# H3BR2.net
KiCad netlist of a schematic drawn in EAGLE
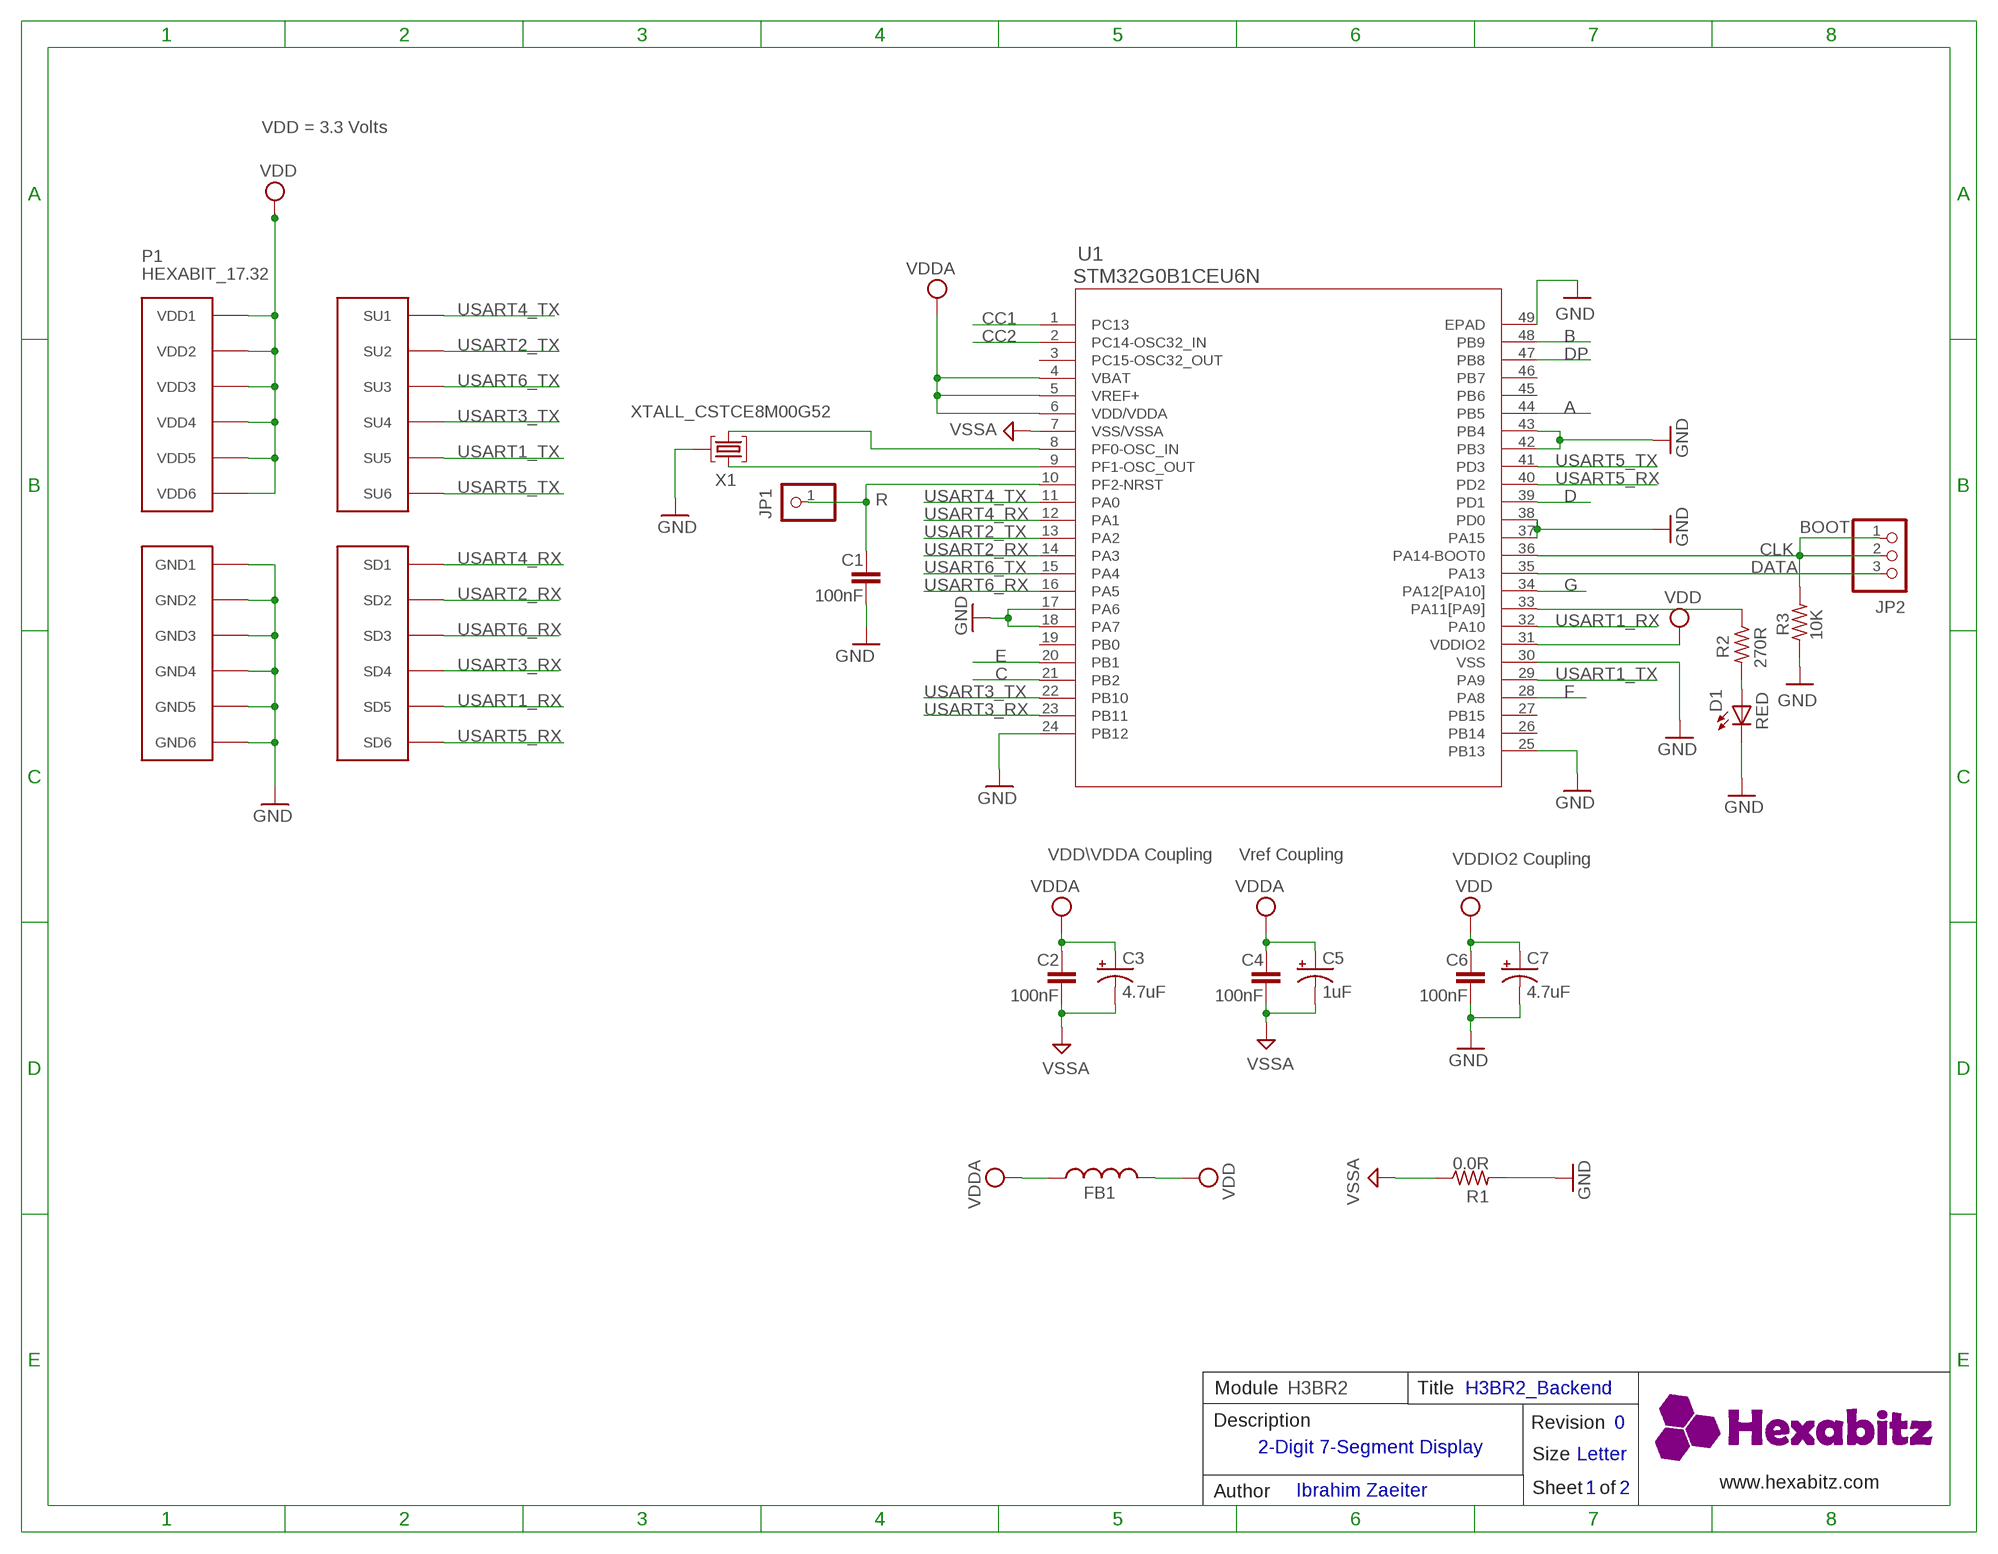
[diagram p0: schematic, sheet 1]
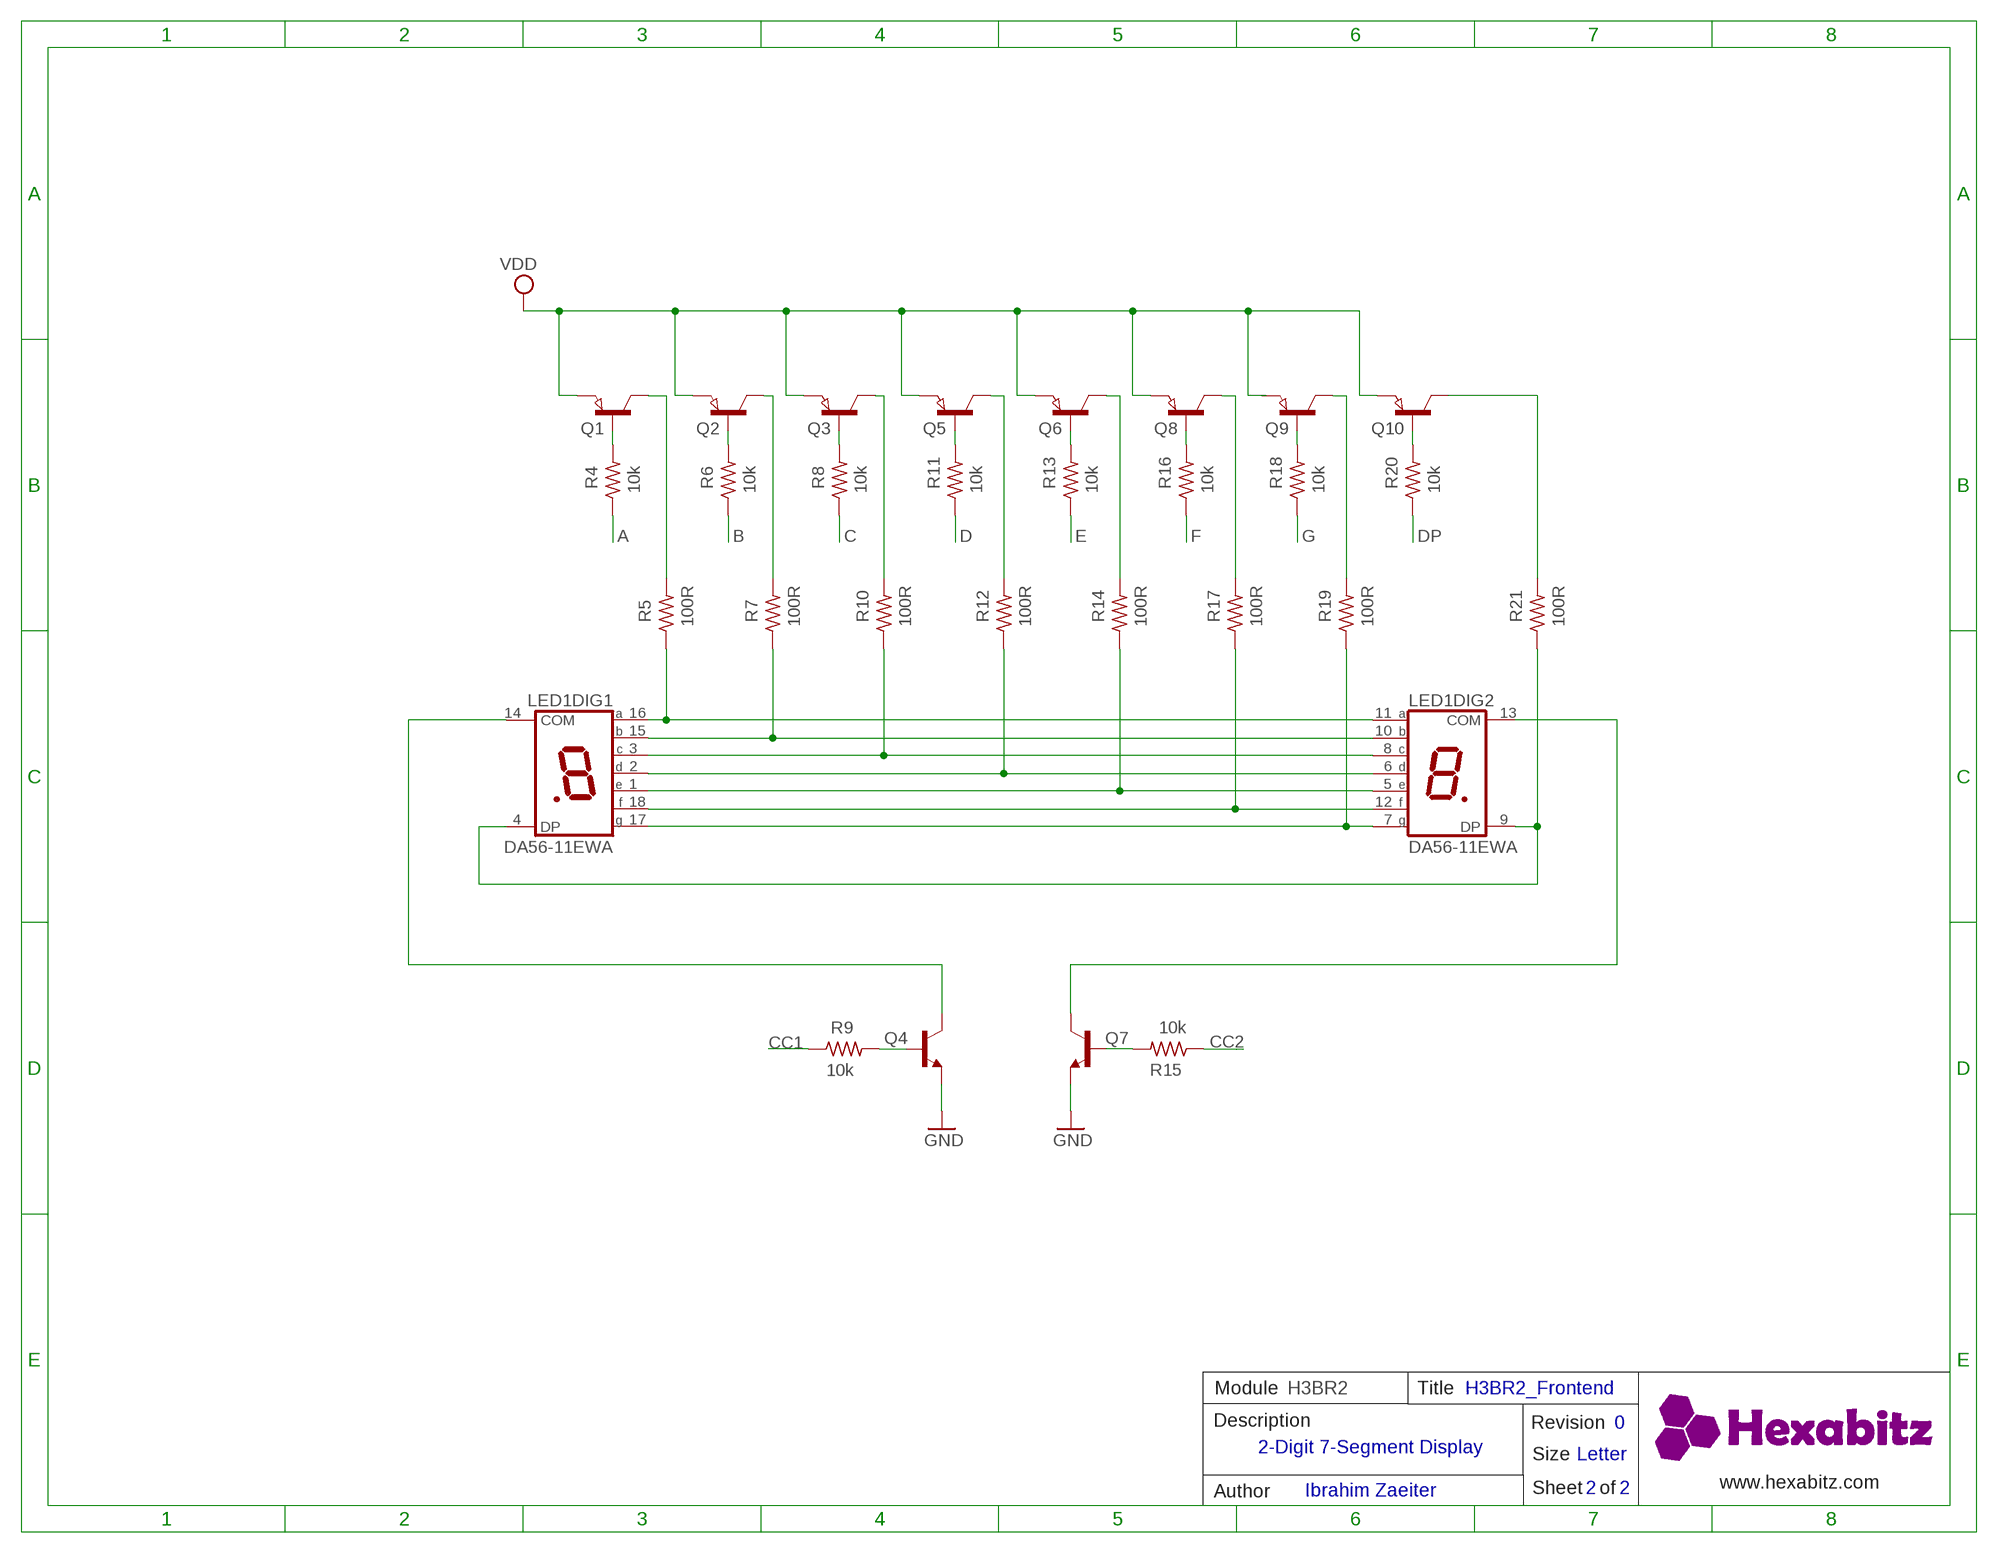
[diagram p1: schematic, sheet 2]

(export (version "E")
  (design (tool "Eeschema 10.0.6"))
  (components
    (comp (ref "C1")
      (value "100nF")
      (footprint "eagle-import:C-0402")
      (libsource (lib "eagle-import") (part "C-0402"))
    )
    (comp (ref "C2")
      (value "100nF")
      (footprint "eagle-import:C-0402")
      (libsource (lib "eagle-import") (part "C-0402"))
    )
    (comp (ref "C3")
      (value "4.7uF")
      (footprint "eagle-import:C-0805-POL")
      (libsource (lib "eagle-import") (part "C-0805-POL"))
    )
    (comp (ref "C4")
      (value "100nF")
      (footprint "eagle-import:C-0402")
      (libsource (lib "eagle-import") (part "C-0402"))
    )
    (comp (ref "C5")
      (value "1uF")
      (footprint "eagle-import:C-0805-POL")
      (libsource (lib "eagle-import") (part "C-0805-POL"))
    )
    (comp (ref "C6")
      (value "100nF")
      (footprint "eagle-import:C-0402")
      (libsource (lib "eagle-import") (part "C-0402"))
    )
    (comp (ref "C7")
      (value "4.7uF")
      (footprint "eagle-import:C-0805-POL")
      (libsource (lib "eagle-import") (part "C-0805-POL"))
    )
    (comp (ref "D1")
      (value "RED")
      (footprint "eagle-import:VLMS1300-GS08")
      (fields
        (field (name "MPN") "VLMS1300-GS08")
        (field (name "MFN") "Vishay")
        (field (name "MPN_1") "VLMS1300-GS08")
        (field (name "OCTOPART_URL") "https://octopart.com/vlms1300-gs08-vishay-21709201?r=sp&s=_gcP4_q8T1SC6PJQPTQ9yA")
      )
      (libsource (lib "eagle-import") (part "VLMS1300-GS08"))
    )
    (comp (ref "FB1")
      (value "FB-0603")
      (footprint "eagle-import:FB-0603")
      (libsource (lib "eagle-import") (part "FB-0603"))
    )
    (comp (ref "JP1")
      (value "R")
      (footprint "eagle-import:1X01")
      (fields (field (name "MPN") "87227-1"))
      (libsource (lib "eagle-import") (part "PINHD-1X1"))
    )
    (comp (ref "JP2")
      (value "PINHD-1X3")
      (footprint "eagle-import:1X03")
      (libsource (lib "eagle-import") (part "PINHD-1X3"))
    )
    (comp (ref "P1")
      (value "HEXABIT_17.32")
      (footprint "eagle-import:HEXABIT_17.32")
      (libsource (lib "eagle-import") (part "HEXABIT_?17.32"))
    )
    (comp (ref "R1")
      (value "0.0R")
      (footprint "eagle-import:R-0402")
      (libsource (lib "eagle-import") (part "R-0402"))
    )
    (comp (ref "R2")
      (value "270R")
      (footprint "eagle-import:R-0603")
      (libsource (lib "eagle-import") (part "R-0603"))
    )
    (comp (ref "R3")
      (value "10K")
      (footprint "eagle-import:R-0402")
      (libsource (lib "eagle-import") (part "R-0402"))
    )
    (comp (ref "U1")
      (value "STM32G0B1CEU6N")
      (footprint "eagle-import:QFN_B1CEU6_STM-L")
      (libsource (lib "eagle-import") (part "STM32G0B1CEU6N"))
    )
    (comp (ref "X1")
      (value "XTALL_CSTCE8M00G52")
      (footprint "eagle-import:XTALL_CSTCE8M00G52")
      (fields (field (name "MPN") "CSTCE8M00G52Z-R0"))
      (libsource (lib "eagle-import") (part "XTALL_CSTCE8M00G52"))
    )
    (comp (ref "LED1")
      (value "DA56-11EWA")
      (footprint "eagle-import:DA56")
      (fields (field (name "MF") "Lite-On") (field (name "MPN") "LTD-6940HR"))
      (libsource (lib "eagle-import") (part "DA56-11EWA"))
    )
    (comp (ref "Q1")
      (value "SEMICON-SMD-IPC_PNP-TRANSISTOR_SOT23")
      (footprint "eagle-import:SEMICON-SMD-IPC_SOT23")
      (libsource (lib "eagle-import") (part "SEMICON-SMD-IPC_PNP-TRANSISTOR_SOT23"))
    )
    (comp (ref "Q2")
      (value "SEMICON-SMD-IPC_PNP-TRANSISTOR_SOT23")
      (footprint "eagle-import:SEMICON-SMD-IPC_SOT23")
      (libsource (lib "eagle-import") (part "SEMICON-SMD-IPC_PNP-TRANSISTOR_SOT23"))
    )
    (comp (ref "Q3")
      (value "SEMICON-SMD-IPC_PNP-TRANSISTOR_SOT23")
      (footprint "eagle-import:SEMICON-SMD-IPC_SOT23")
      (libsource (lib "eagle-import") (part "SEMICON-SMD-IPC_PNP-TRANSISTOR_SOT23"))
    )
    (comp (ref "Q4")
      (value "MMBT3904LT1")
      (footprint "eagle-import:MMBT3904LT1")
      (libsource (lib "eagle-import") (part "MMBT3904LT1"))
    )
    (comp (ref "Q5")
      (value "SEMICON-SMD-IPC_PNP-TRANSISTOR_SOT23")
      (footprint "eagle-import:SEMICON-SMD-IPC_SOT23")
      (libsource (lib "eagle-import") (part "SEMICON-SMD-IPC_PNP-TRANSISTOR_SOT23"))
    )
    (comp (ref "Q6")
      (value "SEMICON-SMD-IPC_PNP-TRANSISTOR_SOT23")
      (footprint "eagle-import:SEMICON-SMD-IPC_SOT23")
      (libsource (lib "eagle-import") (part "SEMICON-SMD-IPC_PNP-TRANSISTOR_SOT23"))
    )
    (comp (ref "Q7")
      (value "MMBT3904LT1")
      (footprint "eagle-import:MMBT3904LT1")
      (libsource (lib "eagle-import") (part "MMBT3904LT1"))
    )
    (comp (ref "Q8")
      (value "SEMICON-SMD-IPC_PNP-TRANSISTOR_SOT23")
      (footprint "eagle-import:SEMICON-SMD-IPC_SOT23")
      (libsource (lib "eagle-import") (part "SEMICON-SMD-IPC_PNP-TRANSISTOR_SOT23"))
    )
    (comp (ref "Q9")
      (value "SEMICON-SMD-IPC_PNP-TRANSISTOR_SOT23")
      (footprint "eagle-import:SEMICON-SMD-IPC_SOT23")
      (libsource (lib "eagle-import") (part "SEMICON-SMD-IPC_PNP-TRANSISTOR_SOT23"))
    )
    (comp (ref "Q10")
      (value "SEMICON-SMD-IPC_PNP-TRANSISTOR_SOT23")
      (footprint "eagle-import:SEMICON-SMD-IPC_SOT23")
      (libsource (lib "eagle-import") (part "SEMICON-SMD-IPC_PNP-TRANSISTOR_SOT23"))
    )
    (comp (ref "R4")
      (value "10k")
      (footprint "eagle-import:R-0402")
      (libsource (lib "eagle-import") (part "R-0402"))
    )
    (comp (ref "R5")
      (value "100R")
      (footprint "eagle-import:R-0402")
      (libsource (lib "eagle-import") (part "R-0402"))
    )
    (comp (ref "R6")
      (value "10k")
      (footprint "eagle-import:R-0402")
      (libsource (lib "eagle-import") (part "R-0402"))
    )
    (comp (ref "R7")
      (value "100R")
      (footprint "eagle-import:R-0402")
      (libsource (lib "eagle-import") (part "R-0402"))
    )
    (comp (ref "R8")
      (value "10k")
      (footprint "eagle-import:R-0402")
      (libsource (lib "eagle-import") (part "R-0402"))
    )
    (comp (ref "R9")
      (value "10k")
      (footprint "eagle-import:R-0402")
      (libsource (lib "eagle-import") (part "R-0402"))
    )
    (comp (ref "R10")
      (value "100R")
      (footprint "eagle-import:R-0402")
      (libsource (lib "eagle-import") (part "R-0402"))
    )
    (comp (ref "R11")
      (value "10k")
      (footprint "eagle-import:R-0402")
      (libsource (lib "eagle-import") (part "R-0402"))
    )
    (comp (ref "R12")
      (value "100R")
      (footprint "eagle-import:R-0402")
      (libsource (lib "eagle-import") (part "R-0402"))
    )
    (comp (ref "R13")
      (value "10k")
      (footprint "eagle-import:R-0402")
      (libsource (lib "eagle-import") (part "R-0402"))
    )
    (comp (ref "R14")
      (value "100R")
      (footprint "eagle-import:R-0402")
      (libsource (lib "eagle-import") (part "R-0402"))
    )
    (comp (ref "R15")
      (value "10k")
      (footprint "eagle-import:R-0402")
      (libsource (lib "eagle-import") (part "R-0402"))
    )
    (comp (ref "R16")
      (value "10k")
      (footprint "eagle-import:R-0402")
      (libsource (lib "eagle-import") (part "R-0402"))
    )
    (comp (ref "R17")
      (value "100R")
      (footprint "eagle-import:R-0402")
      (libsource (lib "eagle-import") (part "R-0402"))
    )
    (comp (ref "R18")
      (value "10k")
      (footprint "eagle-import:R-0402")
      (libsource (lib "eagle-import") (part "R-0402"))
    )
    (comp (ref "R19")
      (value "100R")
      (footprint "eagle-import:R-0402")
      (libsource (lib "eagle-import") (part "R-0402"))
    )
    (comp (ref "R20")
      (value "10k")
      (footprint "eagle-import:R-0402")
      (libsource (lib "eagle-import") (part "R-0402"))
    )
    (comp (ref "R21")
      (value "100R")
      (footprint "eagle-import:R-0402")
      (libsource (lib "eagle-import") (part "R-0402"))
    )
  )
  (nets
    (net (code "1") (name "A") (class "Default")
      (node (ref "R4") (pin "1") (pinfunction "1_1") (pintype "passive"))
      (node (ref "U1") (pin "44") (pinfunction "PB5_44") (pintype "bidirectional"))
    )
    (net (code "2") (name "B") (class "Default")
      (node (ref "R6") (pin "1") (pinfunction "1_1") (pintype "passive"))
      (node (ref "U1") (pin "48") (pinfunction "PB9_48") (pintype "bidirectional"))
    )
    (net (code "3") (name "C") (class "Default")
      (node (ref "R8") (pin "1") (pinfunction "1_1") (pintype "passive"))
      (node (ref "U1") (pin "21") (pinfunction "PB2_21") (pintype "bidirectional"))
    )
    (net (code "4") (name "CC1") (class "Default")
      (node (ref "R9") (pin "1") (pinfunction "1_1") (pintype "passive"))
      (node (ref "U1") (pin "1") (pinfunction "PC13_1") (pintype "bidirectional"))
    )
    (net (code "5") (name "CC2") (class "Default")
      (node (ref "R15") (pin "1") (pinfunction "1_1") (pintype "passive"))
      (node (ref "U1") (pin "2") (pinfunction "PC14-OSC32_IN_2") (pintype "bidirectional"))
    )
    (net (code "6") (name "CLK") (class "Default")
      (node (ref "JP2") (pin "1") (pinfunction "1_1") (pintype "passive"))
      (node (ref "JP2") (pin "2") (pinfunction "2_2") (pintype "passive"))
      (node (ref "R3") (pin "2") (pinfunction "2_2") (pintype "passive"))
      (node (ref "U1") (pin "36") (pinfunction "PA14-BOOT0_36") (pintype "bidirectional"))
    )
    (net (code "7") (name "D") (class "Default")
      (node (ref "R11") (pin "1") (pinfunction "1_1") (pintype "passive"))
      (node (ref "U1") (pin "39") (pinfunction "PD1_39") (pintype "bidirectional"))
    )
    (net (code "8") (name "DATA") (class "Default")
      (node (ref "JP2") (pin "3") (pinfunction "3_3") (pintype "passive"))
      (node (ref "U1") (pin "35") (pinfunction "PA13_35") (pintype "bidirectional"))
    )
    (net (code "9") (name "DP") (class "Default")
      (node (ref "R20") (pin "1") (pinfunction "1_1") (pintype "passive"))
      (node (ref "U1") (pin "47") (pinfunction "PB8_47") (pintype "bidirectional"))
    )
    (net (code "10") (name "E") (class "Default")
      (node (ref "R13") (pin "1") (pinfunction "1_1") (pintype "passive"))
      (node (ref "U1") (pin "20") (pinfunction "PB1_20") (pintype "bidirectional"))
    )
    (net (code "11") (name "F") (class "Default")
      (node (ref "R16") (pin "1") (pinfunction "1_1") (pintype "passive"))
      (node (ref "U1") (pin "28") (pinfunction "PA8_28") (pintype "bidirectional"))
    )
    (net (code "12") (name "G") (class "Default")
      (node (ref "R18") (pin "1") (pinfunction "1_1") (pintype "passive"))
      (node (ref "U1") (pin "34") (pinfunction "PA12[PA10]_34") (pintype "bidirectional"))
    )
    (net (code "13") (name "GND") (class "Default")
      (node (ref "C1") (pin "2") (pinfunction "2_2") (pintype "passive"))
      (node (ref "C6") (pin "2") (pinfunction "2_2") (pintype "passive"))
      (node (ref "C7") (pin "2") (pinfunction "-_2") (pintype "passive"))
      (node (ref "D1") (pin "C") (pinfunction "C_C") (pintype "passive"))
      (node (ref "P1") (pin "PAD_PD10") (pinfunction "GND4_PAD_PD10") (pintype "power_in"))
      (node (ref "P1") (pin "PAD_PD11") (pinfunction "GND5_PAD_PD11") (pintype "power_in"))
      (node (ref "P1") (pin "PAD_PD12") (pinfunction "GND6_PAD_PD12") (pintype "power_in"))
      (node (ref "P1") (pin "PAD_PD7") (pinfunction "GND1_PAD_PD7") (pintype "power_in"))
      (node (ref "P1") (pin "PAD_PD8") (pinfunction "GND2_PAD_PD8") (pintype "power_in"))
      (node (ref "P1") (pin "PAD_PD9") (pinfunction "GND3_PAD_PD9") (pintype "power_in"))
      (node (ref "Q4") (pin "2") (pinfunction "E_2") (pintype "passive"))
      (node (ref "Q7") (pin "2") (pinfunction "E_2") (pintype "passive"))
      (node (ref "R1") (pin "2") (pinfunction "2_2") (pintype "passive"))
      (node (ref "R3") (pin "1") (pinfunction "1_1") (pintype "passive"))
      (node (ref "U1") (pin "17") (pinfunction "PA6_17") (pintype "bidirectional"))
      (node (ref "U1") (pin "18") (pinfunction "PA7_18") (pintype "bidirectional"))
      (node (ref "U1") (pin "24") (pinfunction "PB12_24") (pintype "bidirectional"))
      (node (ref "U1") (pin "25") (pinfunction "PB13_25") (pintype "bidirectional"))
      (node (ref "U1") (pin "30") (pinfunction "VSS_30") (pintype "passive"))
      (node (ref "U1") (pin "37") (pinfunction "PA15_37") (pintype "bidirectional"))
      (node (ref "U1") (pin "38") (pinfunction "PD0_38") (pintype "bidirectional"))
      (node (ref "U1") (pin "42") (pinfunction "PB3_42") (pintype "bidirectional"))
      (node (ref "U1") (pin "43") (pinfunction "PB4_43") (pintype "bidirectional"))
      (node (ref "U1") (pin "49") (pinfunction "EPAD_49") (pintype "passive"))
      (node (ref "X1") (pin "P$2") (pinfunction "2_P$2") (pintype "passive"))
    )
    (net (code "14") (name "Net-(D1-PadA)") (class "Default")
      (node (ref "D1") (pin "A") (pinfunction "A_A") (pintype "passive"))
      (node (ref "R2") (pin "2") (pinfunction "2_2") (pintype "passive"))
    )
    (net (code "15") (name "Net-(LED1A-A)") (class "Default")
      (node (ref "LED1") (pin "11") (pinfunction "A_11") (pintype "passive"))
      (node (ref "LED1") (pin "16") (pinfunction "A_16") (pintype "passive"))
      (node (ref "R5") (pin "1") (pinfunction "1_1") (pintype "passive"))
    )
    (net (code "16") (name "Net-(LED1A-B)") (class "Default")
      (node (ref "LED1") (pin "10") (pinfunction "B_10") (pintype "passive"))
      (node (ref "LED1") (pin "15") (pinfunction "B_15") (pintype "passive"))
      (node (ref "R7") (pin "1") (pinfunction "1_1") (pintype "passive"))
    )
    (net (code "17") (name "Net-(LED1A-C)") (class "Default")
      (node (ref "LED1") (pin "3") (pinfunction "C_3") (pintype "passive"))
      (node (ref "LED1") (pin "8") (pinfunction "C_8") (pintype "passive"))
      (node (ref "R10") (pin "1") (pinfunction "1_1") (pintype "passive"))
    )
    (net (code "18") (name "Net-(LED1A-COM)") (class "Default")
      (node (ref "LED1") (pin "14") (pinfunction "COM_14") (pintype "passive"))
      (node (ref "Q4") (pin "3") (pinfunction "C_3") (pintype "passive"))
    )
    (net (code "19") (name "Net-(LED1A-D)") (class "Default")
      (node (ref "LED1") (pin "2") (pinfunction "D_2") (pintype "passive"))
      (node (ref "LED1") (pin "6") (pinfunction "D_6") (pintype "passive"))
      (node (ref "R12") (pin "1") (pinfunction "1_1") (pintype "passive"))
    )
    (net (code "20") (name "Net-(LED1A-DP)") (class "Default")
      (node (ref "LED1") (pin "4") (pinfunction "DP_4") (pintype "passive"))
      (node (ref "LED1") (pin "9") (pinfunction "DP_9") (pintype "passive"))
      (node (ref "R21") (pin "1") (pinfunction "1_1") (pintype "passive"))
    )
    (net (code "21") (name "Net-(LED1A-E)") (class "Default")
      (node (ref "LED1") (pin "1") (pinfunction "E_1") (pintype "passive"))
      (node (ref "LED1") (pin "5") (pinfunction "E_5") (pintype "passive"))
      (node (ref "R14") (pin "1") (pinfunction "1_1") (pintype "passive"))
    )
    (net (code "22") (name "Net-(LED1A-F)") (class "Default")
      (node (ref "LED1") (pin "12") (pinfunction "F_12") (pintype "passive"))
      (node (ref "LED1") (pin "18") (pinfunction "F_18") (pintype "passive"))
      (node (ref "R17") (pin "1") (pinfunction "1_1") (pintype "passive"))
    )
    (net (code "23") (name "Net-(LED1A-G)") (class "Default")
      (node (ref "LED1") (pin "17") (pinfunction "G_17") (pintype "passive"))
      (node (ref "LED1") (pin "7") (pinfunction "G_7") (pintype "passive"))
      (node (ref "R19") (pin "1") (pinfunction "1_1") (pintype "passive"))
    )
    (net (code "24") (name "Net-(LED1B-COM)") (class "Default")
      (node (ref "LED1") (pin "13") (pinfunction "COM_13") (pintype "passive"))
      (node (ref "Q7") (pin "3") (pinfunction "C_3") (pintype "passive"))
    )
    (net (code "25") (name "Net-(Q1-B)") (class "Default")
      (node (ref "Q1") (pin "1") (pinfunction "B_1") (pintype "passive"))
      (node (ref "R4") (pin "2") (pinfunction "2_2") (pintype "passive"))
    )
    (net (code "26") (name "Net-(Q1-C)") (class "Default")
      (node (ref "Q1") (pin "3") (pinfunction "C_3") (pintype "passive"))
      (node (ref "R5") (pin "2") (pinfunction "2_2") (pintype "passive"))
    )
    (net (code "27") (name "Net-(Q2-B)") (class "Default")
      (node (ref "Q2") (pin "1") (pinfunction "B_1") (pintype "passive"))
      (node (ref "R6") (pin "2") (pinfunction "2_2") (pintype "passive"))
    )
    (net (code "28") (name "Net-(Q2-C)") (class "Default")
      (node (ref "Q2") (pin "3") (pinfunction "C_3") (pintype "passive"))
      (node (ref "R7") (pin "2") (pinfunction "2_2") (pintype "passive"))
    )
    (net (code "29") (name "Net-(Q3-B)") (class "Default")
      (node (ref "Q3") (pin "1") (pinfunction "B_1") (pintype "passive"))
      (node (ref "R8") (pin "2") (pinfunction "2_2") (pintype "passive"))
    )
    (net (code "30") (name "Net-(Q3-C)") (class "Default")
      (node (ref "Q3") (pin "3") (pinfunction "C_3") (pintype "passive"))
      (node (ref "R10") (pin "2") (pinfunction "2_2") (pintype "passive"))
    )
    (net (code "31") (name "Net-(Q4-B)") (class "Default")
      (node (ref "Q4") (pin "1") (pinfunction "B_1") (pintype "passive"))
      (node (ref "R9") (pin "2") (pinfunction "2_2") (pintype "passive"))
    )
    (net (code "32") (name "Net-(Q5-B)") (class "Default")
      (node (ref "Q5") (pin "1") (pinfunction "B_1") (pintype "passive"))
      (node (ref "R11") (pin "2") (pinfunction "2_2") (pintype "passive"))
    )
    (net (code "33") (name "Net-(Q5-C)") (class "Default")
      (node (ref "Q5") (pin "3") (pinfunction "C_3") (pintype "passive"))
      (node (ref "R12") (pin "2") (pinfunction "2_2") (pintype "passive"))
    )
    (net (code "34") (name "Net-(Q6-B)") (class "Default")
      (node (ref "Q6") (pin "1") (pinfunction "B_1") (pintype "passive"))
      (node (ref "R13") (pin "2") (pinfunction "2_2") (pintype "passive"))
    )
    (net (code "35") (name "Net-(Q6-C)") (class "Default")
      (node (ref "Q6") (pin "3") (pinfunction "C_3") (pintype "passive"))
      (node (ref "R14") (pin "2") (pinfunction "2_2") (pintype "passive"))
    )
    (net (code "36") (name "Net-(Q7-B)") (class "Default")
      (node (ref "Q7") (pin "1") (pinfunction "B_1") (pintype "passive"))
      (node (ref "R15") (pin "2") (pinfunction "2_2") (pintype "passive"))
    )
    (net (code "37") (name "Net-(Q8-B)") (class "Default")
      (node (ref "Q8") (pin "1") (pinfunction "B_1") (pintype "passive"))
      (node (ref "R16") (pin "2") (pinfunction "2_2") (pintype "passive"))
    )
    (net (code "38") (name "Net-(Q8-C)") (class "Default")
      (node (ref "Q8") (pin "3") (pinfunction "C_3") (pintype "passive"))
      (node (ref "R17") (pin "2") (pinfunction "2_2") (pintype "passive"))
    )
    (net (code "39") (name "Net-(Q9-B)") (class "Default")
      (node (ref "Q9") (pin "1") (pinfunction "B_1") (pintype "passive"))
      (node (ref "R18") (pin "2") (pinfunction "2_2") (pintype "passive"))
    )
    (net (code "40") (name "Net-(Q9-C)") (class "Default")
      (node (ref "Q9") (pin "3") (pinfunction "C_3") (pintype "passive"))
      (node (ref "R19") (pin "2") (pinfunction "2_2") (pintype "passive"))
    )
    (net (code "41") (name "Net-(Q10-B)") (class "Default")
      (node (ref "Q10") (pin "1") (pinfunction "B_1") (pintype "passive"))
      (node (ref "R20") (pin "2") (pinfunction "2_2") (pintype "passive"))
    )
    (net (code "42") (name "Net-(Q10-C)") (class "Default")
      (node (ref "Q10") (pin "3") (pinfunction "C_3") (pintype "passive"))
      (node (ref "R21") (pin "2") (pinfunction "2_2") (pintype "passive"))
    )
    (net (code "43") (name "Net-(U1-PA11[PA9])") (class "Default")
      (node (ref "R2") (pin "1") (pinfunction "1_1") (pintype "passive"))
      (node (ref "U1") (pin "33") (pinfunction "PA11[PA9]_33") (pintype "bidirectional"))
    )
    (net (code "44") (name "Net-(U1-PF0-OSC_IN)") (class "Default")
      (node (ref "U1") (pin "8") (pinfunction "PF0-OSC_IN_8") (pintype "bidirectional"))
      (node (ref "X1") (pin "P$3") (pinfunction "3_P$3") (pintype "passive"))
    )
    (net (code "45") (name "Net-(U1-PF1-OSC_OUT)") (class "Default")
      (node (ref "U1") (pin "9") (pinfunction "PF1-OSC_OUT_9") (pintype "bidirectional"))
      (node (ref "X1") (pin "P$1") (pinfunction "1_P$1") (pintype "passive"))
    )
    (net (code "46") (name "Net-(U1-PF2-NRST)") (class "Default")
      (node (ref "C1") (pin "1") (pinfunction "1_1") (pintype "passive"))
      (node (ref "JP1") (pin "1") (pinfunction "1_1") (pintype "passive"))
      (node (ref "U1") (pin "10") (pinfunction "PF2-NRST_10") (pintype "bidirectional"))
    )
    (net (code "47") (name "USART1_RX") (class "Default")
      (node (ref "P1") (pin "PAD_PD5") (pinfunction "SD5_PAD_PD5") (pintype "bidirectional"))
      (node (ref "U1") (pin "32") (pinfunction "PA10_32") (pintype "bidirectional"))
    )
    (net (code "48") (name "USART1_TX") (class "Default")
      (node (ref "P1") (pin "PAD_PU5") (pinfunction "SU5_PAD_PU5") (pintype "bidirectional"))
      (node (ref "U1") (pin "29") (pinfunction "PA9_29") (pintype "bidirectional"))
    )
    (net (code "49") (name "USART2_RX") (class "Default")
      (node (ref "P1") (pin "PAD_PD2") (pinfunction "SD2_PAD_PD2") (pintype "bidirectional"))
      (node (ref "U1") (pin "14") (pinfunction "PA3_14") (pintype "bidirectional"))
    )
    (net (code "50") (name "USART2_TX") (class "Default")
      (node (ref "P1") (pin "PAD_PU2") (pinfunction "SU2_PAD_PU2") (pintype "bidirectional"))
      (node (ref "U1") (pin "13") (pinfunction "PA2_13") (pintype "bidirectional"))
    )
    (net (code "51") (name "USART3_RX") (class "Default")
      (node (ref "P1") (pin "PAD_PD4") (pinfunction "SD4_PAD_PD4") (pintype "bidirectional"))
      (node (ref "U1") (pin "23") (pinfunction "PB11_23") (pintype "bidirectional"))
    )
    (net (code "52") (name "USART3_TX") (class "Default")
      (node (ref "P1") (pin "PAD_PU4") (pinfunction "SU4_PAD_PU4") (pintype "bidirectional"))
      (node (ref "U1") (pin "22") (pinfunction "PB10_22") (pintype "bidirectional"))
    )
    (net (code "53") (name "USART4_RX") (class "Default")
      (node (ref "P1") (pin "PAD_PD1") (pinfunction "SD1_PAD_PD1") (pintype "bidirectional"))
      (node (ref "U1") (pin "12") (pinfunction "PA1_12") (pintype "bidirectional"))
    )
    (net (code "54") (name "USART4_TX") (class "Default")
      (node (ref "P1") (pin "PAD_PU1") (pinfunction "SU1_PAD_PU1") (pintype "bidirectional"))
      (node (ref "U1") (pin "11") (pinfunction "PA0_11") (pintype "bidirectional"))
    )
    (net (code "55") (name "USART5_RX") (class "Default")
      (node (ref "P1") (pin "PAD_PD6") (pinfunction "SD6_PAD_PD6") (pintype "bidirectional"))
      (node (ref "U1") (pin "40") (pinfunction "PD2_40") (pintype "bidirectional"))
    )
    (net (code "56") (name "USART5_TX") (class "Default")
      (node (ref "P1") (pin "PAD_PU6") (pinfunction "SU6_PAD_PU6") (pintype "bidirectional"))
      (node (ref "U1") (pin "41") (pinfunction "PD3_41") (pintype "bidirectional"))
    )
    (net (code "57") (name "USART6_RX") (class "Default")
      (node (ref "P1") (pin "PAD_PD3") (pinfunction "SD3_PAD_PD3") (pintype "bidirectional"))
      (node (ref "U1") (pin "16") (pinfunction "PA5_16") (pintype "bidirectional"))
    )
    (net (code "58") (name "USART6_TX") (class "Default")
      (node (ref "P1") (pin "PAD_PU3") (pinfunction "SU3_PAD_PU3") (pintype "bidirectional"))
      (node (ref "U1") (pin "15") (pinfunction "PA4_15") (pintype "bidirectional"))
    )
    (net (code "59") (name "VDD") (class "Default")
      (node (ref "C6") (pin "1") (pinfunction "1_1") (pintype "passive"))
      (node (ref "C7") (pin "1") (pinfunction "+_1") (pintype "passive"))
      (node (ref "FB1") (pin "2") (pinfunction "2_2") (pintype "passive"))
      (node (ref "P1") (pin "PAD_PU10") (pinfunction "VDD4_PAD_PU10") (pintype "power_in"))
      (node (ref "P1") (pin "PAD_PU11") (pinfunction "VDD5_PAD_PU11") (pintype "power_in"))
      (node (ref "P1") (pin "PAD_PU12") (pinfunction "VDD6_PAD_PU12") (pintype "power_in"))
      (node (ref "P1") (pin "PAD_PU7") (pinfunction "VDD1_PAD_PU7") (pintype "power_in"))
      (node (ref "P1") (pin "PAD_PU8") (pinfunction "VDD2_PAD_PU8") (pintype "power_in"))
      (node (ref "P1") (pin "PAD_PU9") (pinfunction "VDD3_PAD_PU9") (pintype "power_in"))
      (node (ref "Q1") (pin "2") (pinfunction "E_2") (pintype "passive"))
      (node (ref "Q10") (pin "2") (pinfunction "E_2") (pintype "passive"))
      (node (ref "Q2") (pin "2") (pinfunction "E_2") (pintype "passive"))
      (node (ref "Q3") (pin "2") (pinfunction "E_2") (pintype "passive"))
      (node (ref "Q5") (pin "2") (pinfunction "E_2") (pintype "passive"))
      (node (ref "Q6") (pin "2") (pinfunction "E_2") (pintype "passive"))
      (node (ref "Q8") (pin "2") (pinfunction "E_2") (pintype "passive"))
      (node (ref "Q9") (pin "2") (pinfunction "E_2") (pintype "passive"))
      (node (ref "U1") (pin "31") (pinfunction "VDDIO2_31") (pintype "power_in"))
    )
    (net (code "60") (name "VDDA") (class "Default")
      (node (ref "C2") (pin "1") (pinfunction "1_1") (pintype "passive"))
      (node (ref "C3") (pin "1") (pinfunction "+_1") (pintype "passive"))
      (node (ref "C4") (pin "1") (pinfunction "1_1") (pintype "passive"))
      (node (ref "C5") (pin "1") (pinfunction "+_1") (pintype "passive"))
      (node (ref "FB1") (pin "1") (pinfunction "1_1") (pintype "passive"))
      (node (ref "U1") (pin "4") (pinfunction "VBAT_4") (pintype "power_in"))
      (node (ref "U1") (pin "5") (pinfunction "VREF+_5") (pintype "power_in"))
      (node (ref "U1") (pin "6") (pinfunction "VDD/VDDA_6") (pintype "power_in"))
    )
    (net (code "61") (name "VSSA") (class "Default")
      (node (ref "C2") (pin "2") (pinfunction "2_2") (pintype "passive"))
      (node (ref "C3") (pin "2") (pinfunction "-_2") (pintype "passive"))
      (node (ref "C4") (pin "2") (pinfunction "2_2") (pintype "passive"))
      (node (ref "C5") (pin "2") (pinfunction "-_2") (pintype "passive"))
      (node (ref "R1") (pin "1") (pinfunction "1_1") (pintype "passive"))
      (node (ref "U1") (pin "7") (pinfunction "VSS/VSSA_7") (pintype "passive"))
    )
    (net (code "62") (name "unconnected-(U1-PB0-Pad19)") (class "Default")
      (node (ref "U1") (pin "19") (pinfunction "PB0_19") (pintype "bidirectional"))
    )
    (net (code "63") (name "unconnected-(U1-PB6-Pad45)") (class "Default")
      (node (ref "U1") (pin "45") (pinfunction "PB6_45") (pintype "bidirectional"))
    )
    (net (code "64") (name "unconnected-(U1-PB7-Pad46)") (class "Default")
      (node (ref "U1") (pin "46") (pinfunction "PB7_46") (pintype "bidirectional"))
    )
    (net (code "65") (name "unconnected-(U1-PB14-Pad26)") (class "Default")
      (node (ref "U1") (pin "26") (pinfunction "PB14_26") (pintype "bidirectional"))
    )
    (net (code "66") (name "unconnected-(U1-PB15-Pad27)") (class "Default")
      (node (ref "U1") (pin "27") (pinfunction "PB15_27") (pintype "bidirectional"))
    )
    (net (code "67") (name "unconnected-(U1-PC15-OSC32_OUT-Pad3)") (class "Default")
      (node (ref "U1") (pin "3") (pinfunction "PC15-OSC32_OUT_3") (pintype "bidirectional"))
    )
  )
)
